# ReflectiveIR.net
KiCad netlist of a schematic drawn in EAGLE
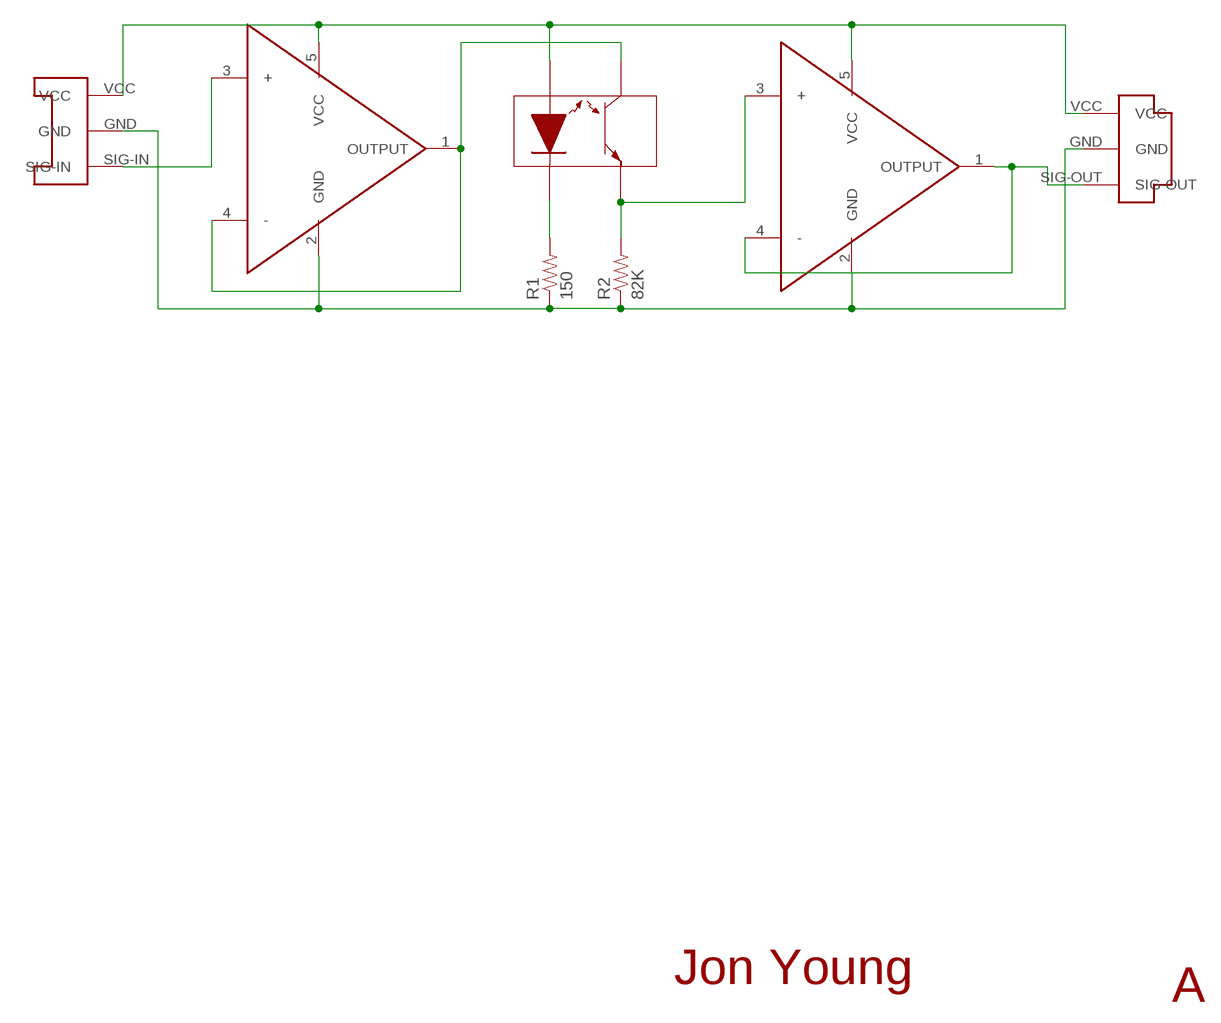
[diagram p0: schematic, sheet 1]

(export (version "E")
  (design (tool "Eeschema 10.0.6"))
  (components
    (comp (ref "R1")
      (value "150")
      (footprint "eagle-import:0603-RES")
      (libsource (lib "eagle-import") (part "RESISTOR0603"))
    )
    (comp (ref "R2")
      (value "82K")
      (footprint "eagle-import:0603-RES")
      (libsource (lib "eagle-import") (part "RESISTOR0603"))
    )
    (comp (ref "U$1")
      (value "CONN-PLUG-3POS-3MM")
      (footprint "eagle-import:PLUG-3POS-3MM-SMD")
      (libsource (lib "eagle-import") (part "CONN-PLUG-3POS-3MM"))
    )
    (comp (ref "U$2")
      (value "CONN-SOCKET-3POS-3MM")
      (footprint "eagle-import:SOCKET-3POS-3MM-SMD")
      (libsource (lib "eagle-import") (part "CONN-SOCKET-3POS-3MM"))
    )
    (comp (ref "U$3")
      (value "REFLECTIVE-SENSOR-OPB733TR")
      (footprint "eagle-import:REFLECTIVE-SENSOR-OPB733TR")
      (libsource (lib "eagle-import") (part "REFLECTIVE-SENSOR-OPB733TR"))
    )
    (comp (ref "U$4")
      (value "OPAMP-MCP6001SC70-5")
      (footprint "eagle-import:SC70")
      (libsource (lib "eagle-import") (part "OPAMP-MCP6001SC70-5"))
    )
    (comp (ref "U$5")
      (value "OPAMP-MCP6001SC70-5")
      (footprint "eagle-import:SC70")
      (libsource (lib "eagle-import") (part "OPAMP-MCP6001SC70-5"))
    )
  )
  (nets
    (net (code "1") (name "Net-(R1-Pad2)") (class "Default")
      (node (ref "R1") (pin "2") (pinfunction "2_2") (pintype "passive"))
      (node (ref "U$3") (pin "P1-CATHODE") (pinfunction "P1-CATHODE_P1-CATHODE") (pintype "passive"))
    )
    (net (code "2") (name "Net-(U$4-+)") (class "Default")
      (node (ref "U$2") (pin "SIG-IN") (pinfunction "SIG-IN_SIG-IN") (pintype "bidirectional"))
      (node (ref "U$4") (pin "3") (pinfunction "+_3") (pintype "input"))
    )
    (net (code "3") (name "Net-(U$4--)") (class "Default")
      (node (ref "U$3") (pin "P3-COLLECTOR") (pinfunction "P3-COLLECTOR_P3-COLLECTOR") (pintype "passive"))
      (node (ref "U$4") (pin "1") (pinfunction "OUTPUT_1") (pintype "output"))
      (node (ref "U$4") (pin "4") (pinfunction "-_4") (pintype "input"))
    )
    (net (code "4") (name "Net-(U$4-GND)") (class "Default")
      (node (ref "R1") (pin "1") (pinfunction "1_1") (pintype "passive"))
      (node (ref "R2") (pin "1") (pinfunction "1_1") (pintype "passive"))
      (node (ref "U$1") (pin "GND") (pinfunction "GND_GND") (pintype "power_in"))
      (node (ref "U$2") (pin "GND") (pinfunction "GND_GND") (pintype "power_in"))
      (node (ref "U$4") (pin "2") (pinfunction "GND_2") (pintype "power_in"))
      (node (ref "U$5") (pin "2") (pinfunction "GND_2") (pintype "power_in"))
    )
    (net (code "5") (name "Net-(U$4-VCC)") (class "Default")
      (node (ref "U$1") (pin "VCC") (pinfunction "VCC_VCC") (pintype "power_in"))
      (node (ref "U$2") (pin "VCC") (pinfunction "VCC_VCC") (pintype "power_in"))
      (node (ref "U$3") (pin "P4-ANODE") (pinfunction "P4-ANODE_P4-ANODE") (pintype "passive"))
      (node (ref "U$4") (pin "5") (pinfunction "VCC_5") (pintype "power_in"))
      (node (ref "U$5") (pin "5") (pinfunction "VCC_5") (pintype "power_in"))
    )
    (net (code "6") (name "Net-(U$5-+)") (class "Default")
      (node (ref "R2") (pin "2") (pinfunction "2_2") (pintype "passive"))
      (node (ref "U$3") (pin "P2-EMITTER") (pinfunction "P2-EMITTER_P2-EMITTER") (pintype "passive"))
      (node (ref "U$5") (pin "3") (pinfunction "+_3") (pintype "input"))
    )
    (net (code "7") (name "Net-(U$5--)") (class "Default")
      (node (ref "U$1") (pin "SIG-OUT") (pinfunction "SIG-OUT_SIG-OUT") (pintype "bidirectional"))
      (node (ref "U$5") (pin "1") (pinfunction "OUTPUT_1") (pintype "output"))
      (node (ref "U$5") (pin "4") (pinfunction "-_4") (pintype "input"))
    )
  )
)
